# jar-of-fireflies.net
KiCad netlist of a schematic drawn in EAGLE
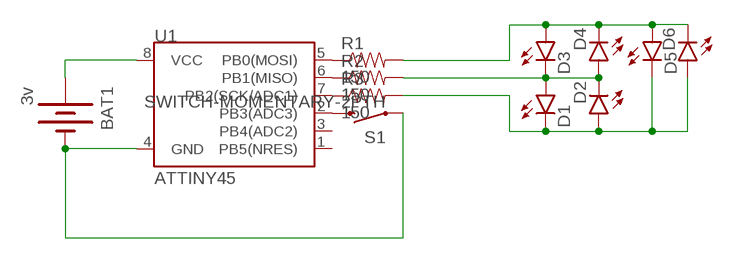
[diagram p0: schematic, sheet 1]

(export (version "E")
  (design (tool "Eeschema 10.0.6"))
  (components
    (comp (ref "BAT1")
      (value "3v")
      (footprint "eagle-import:BATTCOM_20MM_PTH")
      (libsource (lib "eagle-import") (part "BATTERY20PTH"))
    )
    (comp (ref "D1")
      (value "LED3MM")
      (footprint "eagle-import:LED3MM")
      (libsource (lib "eagle-import") (part "LED3MM"))
    )
    (comp (ref "D2")
      (value "LED3MM")
      (footprint "eagle-import:LED3MM")
      (libsource (lib "eagle-import") (part "LED3MM"))
    )
    (comp (ref "D3")
      (value "LED3MM")
      (footprint "eagle-import:LED3MM")
      (libsource (lib "eagle-import") (part "LED3MM"))
    )
    (comp (ref "D4")
      (value "LED3MM")
      (footprint "eagle-import:LED3MM")
      (libsource (lib "eagle-import") (part "LED3MM"))
    )
    (comp (ref "D5")
      (value "LED3MM")
      (footprint "eagle-import:LED3MM")
      (libsource (lib "eagle-import") (part "LED3MM"))
    )
    (comp (ref "D6")
      (value "LED3MM")
      (footprint "eagle-import:LED3MM")
      (libsource (lib "eagle-import") (part "LED3MM"))
    )
    (comp (ref "R1")
      (value "150")
      (footprint "eagle-import:AXIAL-0.4")
      (libsource (lib "eagle-import") (part "RESISTORPTH-1/4W"))
    )
    (comp (ref "R2")
      (value "150")
      (footprint "eagle-import:AXIAL-0.4")
      (libsource (lib "eagle-import") (part "RESISTORPTH-1/4W"))
    )
    (comp (ref "R3")
      (value "150")
      (footprint "eagle-import:AXIAL-0.4")
      (libsource (lib "eagle-import") (part "RESISTORPTH-1/4W"))
    )
    (comp (ref "S1")
      (value "SWITCH-MOMENTARY-2PTH")
      (footprint "eagle-import:TACTILE-PTH")
      (libsource (lib "eagle-import") (part "SWITCH-MOMENTARY-2PTH"))
    )
    (comp (ref "U1")
      (value "ATTINY45")
      (footprint "eagle-import:DIP08")
      (libsource (lib "eagle-import") (part "ATTINY45TINY85-20-DIP"))
    )
  )
  (nets
    (net (code "1") (name "Net-(BAT1-+)") (class "Default")
      (node (ref "BAT1") (pin "1") (pinfunction "+_1") (pintype "power_in"))
      (node (ref "U1") (pin "8") (pinfunction "VCC_8") (pintype "bidirectional"))
    )
    (net (code "2") (name "Net-(BAT1--)") (class "Default")
      (node (ref "BAT1") (pin "2") (pinfunction "-_2") (pintype "power_in"))
      (node (ref "S1") (pin "1") (pinfunction "1_1") (pintype "passive"))
      (node (ref "U1") (pin "4") (pinfunction "GND_4") (pintype "bidirectional"))
    )
    (net (code "3") (name "Net-(D1-C)") (class "Default")
      (node (ref "D1") (pin "K") (pinfunction "C_K") (pintype "passive"))
      (node (ref "D2") (pin "A") (pinfunction "A_A") (pintype "passive"))
      (node (ref "D5") (pin "K") (pinfunction "C_K") (pintype "passive"))
      (node (ref "D6") (pin "A") (pinfunction "A_A") (pintype "passive"))
      (node (ref "R3") (pin "P$2") (pinfunction "2_P$2") (pintype "passive"))
    )
    (net (code "4") (name "Net-(D2-C)") (class "Default")
      (node (ref "D1") (pin "A") (pinfunction "A_A") (pintype "passive"))
      (node (ref "D2") (pin "K") (pinfunction "C_K") (pintype "passive"))
      (node (ref "D3") (pin "K") (pinfunction "C_K") (pintype "passive"))
      (node (ref "D4") (pin "A") (pinfunction "A_A") (pintype "passive"))
      (node (ref "R2") (pin "P$2") (pinfunction "2_P$2") (pintype "passive"))
    )
    (net (code "5") (name "Net-(D4-C)") (class "Default")
      (node (ref "D3") (pin "A") (pinfunction "A_A") (pintype "passive"))
      (node (ref "D4") (pin "K") (pinfunction "C_K") (pintype "passive"))
      (node (ref "D5") (pin "A") (pinfunction "A_A") (pintype "passive"))
      (node (ref "D6") (pin "K") (pinfunction "C_K") (pintype "passive"))
      (node (ref "R1") (pin "P$2") (pinfunction "2_P$2") (pintype "passive"))
    )
    (net (code "6") (name "Net-(R1-1)") (class "Default")
      (node (ref "R1") (pin "P$1") (pinfunction "1_P$1") (pintype "passive"))
      (node (ref "U1") (pin "5") (pinfunction "PB0(MOSI)_5") (pintype "bidirectional"))
    )
    (net (code "7") (name "Net-(R2-1)") (class "Default")
      (node (ref "R2") (pin "P$1") (pinfunction "1_P$1") (pintype "passive"))
      (node (ref "U1") (pin "6") (pinfunction "PB1(MISO)_6") (pintype "bidirectional"))
    )
    (net (code "8") (name "Net-(R3-1)") (class "Default")
      (node (ref "R3") (pin "P$1") (pinfunction "1_P$1") (pintype "passive"))
      (node (ref "U1") (pin "7") (pinfunction "PB2(SCK/ADC1)_7") (pintype "bidirectional"))
    )
    (net (code "9") (name "Net-(S1-2)") (class "Default")
      (node (ref "S1") (pin "3") (pinfunction "2_3") (pintype "passive"))
      (node (ref "U1") (pin "2") (pinfunction "PB3(ADC3)_2") (pintype "bidirectional"))
    )
    (net (code "10") (name "unconnected-(U1-PB4(ADC2)-Pad3)") (class "Default")
      (node (ref "U1") (pin "3") (pinfunction "PB4(ADC2)_3") (pintype "bidirectional"))
    )
    (net (code "11") (name "unconnected-(U1-PB5(NRES)-Pad1)") (class "Default")
      (node (ref "U1") (pin "1") (pinfunction "PB5(NRES)_1") (pintype "bidirectional"))
    )
  )
)
